# stepdowen.net
KiCad netlist of a schematic drawn in EAGLE
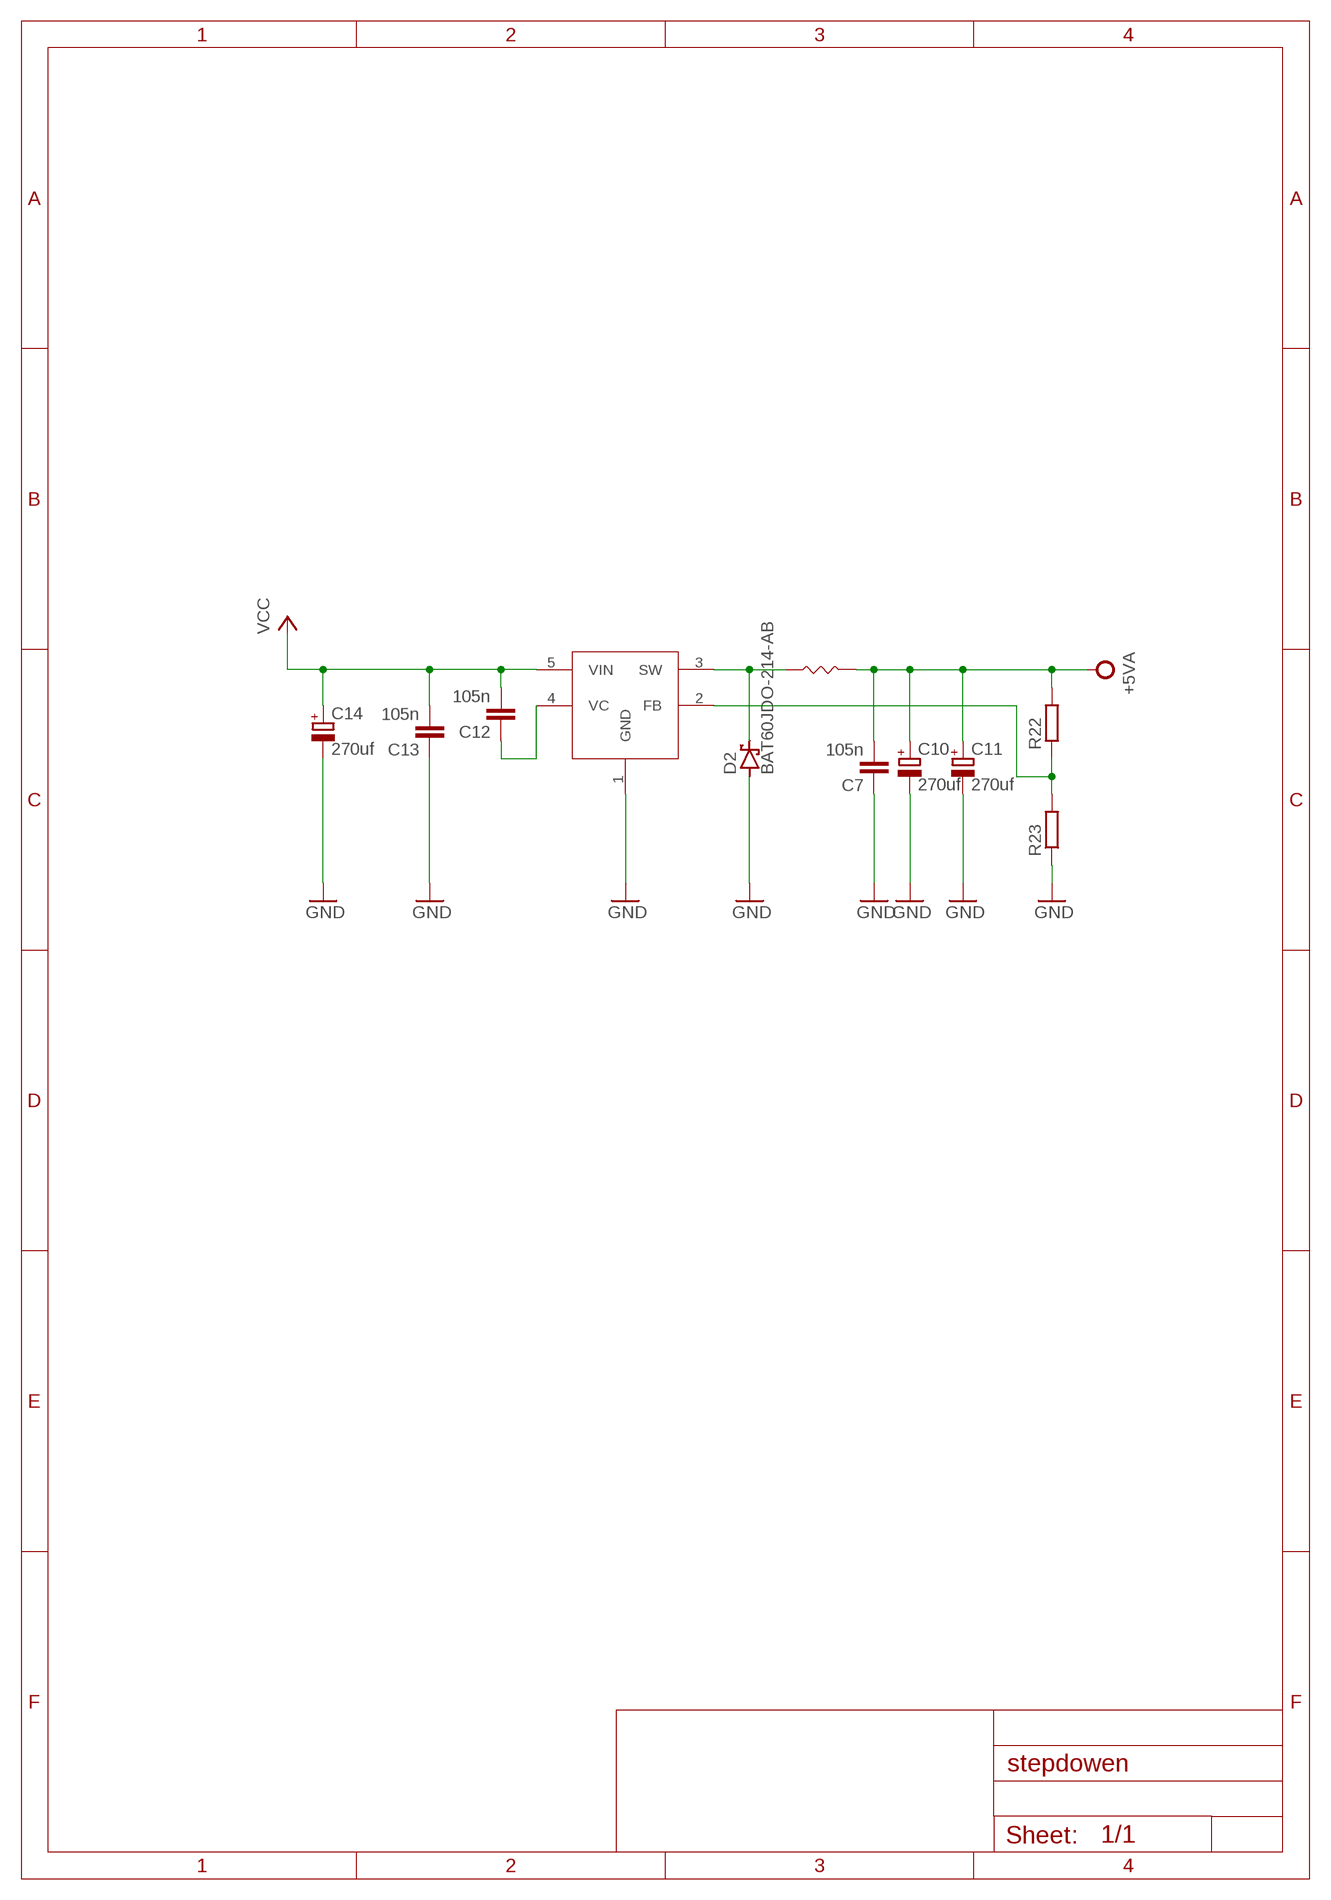
[diagram p0: schematic, sheet 1]

(export (version "E")
  (design (tool "Eeschema 10.0.6"))
  (components
    (comp (ref "C7")
      (value "105n")
      (footprint "eagle-import:C0603")
      (libsource (lib "eagle-import") (part "C-EUC0603"))
    )
    (comp (ref "C10")
      (value "270uf")
      (footprint "eagle-import:140CLH-1010")
      (libsource (lib "eagle-import") (part "CPOL-EU140CLH-1010"))
    )
    (comp (ref "C11")
      (value "270uf")
      (footprint "eagle-import:140CLH-1010")
      (libsource (lib "eagle-import") (part "CPOL-EU140CLH-1010"))
    )
    (comp (ref "C12")
      (value "105n")
      (footprint "eagle-import:C0603")
      (libsource (lib "eagle-import") (part "C-EUC0603"))
    )
    (comp (ref "C13")
      (value "105n")
      (footprint "eagle-import:C0603")
      (libsource (lib "eagle-import") (part "C-EUC0603"))
    )
    (comp (ref "C14")
      (value "270uf")
      (footprint "eagle-import:140CLH-1010")
      (libsource (lib "eagle-import") (part "CPOL-EU140CLH-1010"))
    )
    (comp (ref "D2")
      (value "BAT60JDO-214-AB")
      (footprint "eagle-import:DO214BA")
      (libsource (lib "eagle-import") (part "BAT60JDO-214-AB"))
    )
    (comp (ref "R22")
      (value "R-EU_R0402")
      (footprint "eagle-import:R0402")
      (libsource (lib "eagle-import") (part "R-EU_R0402"))
    )
    (comp (ref "R23")
      (value "R-EU_R0402")
      (footprint "eagle-import:R0402")
      (libsource (lib "eagle-import") (part "R-EU_R0402"))
    )
    (comp (ref "U$2")
      (value "LX4015")
      (footprint "eagle-import:TO-263-5")
      (libsource (lib "eagle-import") (part "LX4015"))
    )
    (comp (ref "U$3")
      (value "SRP1265")
      (footprint "eagle-import:3R3-1510")
      (libsource (lib "eagle-import") (part "SRP1265"))
    )
  )
  (nets
    (net (code "1") (name "+5VA") (class "Default")
      (node (ref "C10") (pin "+") (pinfunction "+_+") (pintype "passive"))
      (node (ref "C11") (pin "+") (pinfunction "+_+") (pintype "passive"))
      (node (ref "C7") (pin "2") (pinfunction "2_2") (pintype "passive"))
      (node (ref "R22") (pin "2") (pinfunction "2_2") (pintype "passive"))
      (node (ref "U$3") (pin "P$2") (pinfunction "P$2_P$2") (pintype "bidirectional"))
    )
    (net (code "2") (name "GND") (class "Default")
      (node (ref "C10") (pin "-") (pinfunction "-_-") (pintype "passive"))
      (node (ref "C11") (pin "-") (pinfunction "-_-") (pintype "passive"))
      (node (ref "C13") (pin "1") (pinfunction "1_1") (pintype "passive"))
      (node (ref "C14") (pin "-") (pinfunction "-_-") (pintype "passive"))
      (node (ref "C7") (pin "1") (pinfunction "1_1") (pintype "passive"))
      (node (ref "D2") (pin "A") (pinfunction "A_A") (pintype "passive"))
      (node (ref "R23") (pin "1") (pinfunction "1_1") (pintype "passive"))
      (node (ref "U$2") (pin "1") (pinfunction "GND_1") (pintype "bidirectional"))
    )
    (net (code "3") (name "Net-(U$2-FB)") (class "Default")
      (node (ref "R22") (pin "1") (pinfunction "1_1") (pintype "passive"))
      (node (ref "R23") (pin "2") (pinfunction "2_2") (pintype "passive"))
      (node (ref "U$2") (pin "2") (pinfunction "FB_2") (pintype "bidirectional"))
    )
    (net (code "4") (name "Net-(U$2-SW)") (class "Default")
      (node (ref "D2") (pin "C") (pinfunction "C_C") (pintype "passive"))
      (node (ref "U$2") (pin "3") (pinfunction "SW_3") (pintype "bidirectional"))
      (node (ref "U$3") (pin "P$1") (pinfunction "P$1_P$1") (pintype "bidirectional"))
    )
    (net (code "5") (name "Net-(U$2-VC)") (class "Default")
      (node (ref "C12") (pin "1") (pinfunction "1_1") (pintype "passive"))
      (node (ref "U$2") (pin "4") (pinfunction "VC_4") (pintype "bidirectional"))
    )
    (net (code "6") (name "VCC") (class "Default")
      (node (ref "C12") (pin "2") (pinfunction "2_2") (pintype "passive"))
      (node (ref "C13") (pin "2") (pinfunction "2_2") (pintype "passive"))
      (node (ref "C14") (pin "+") (pinfunction "+_+") (pintype "passive"))
      (node (ref "U$2") (pin "5") (pinfunction "VIN_5") (pintype "bidirectional"))
    )
  )
)
